# SMT-PBTSv1_4_Schematic.net
KiCad netlist of a schematic drawn in EasyEDA
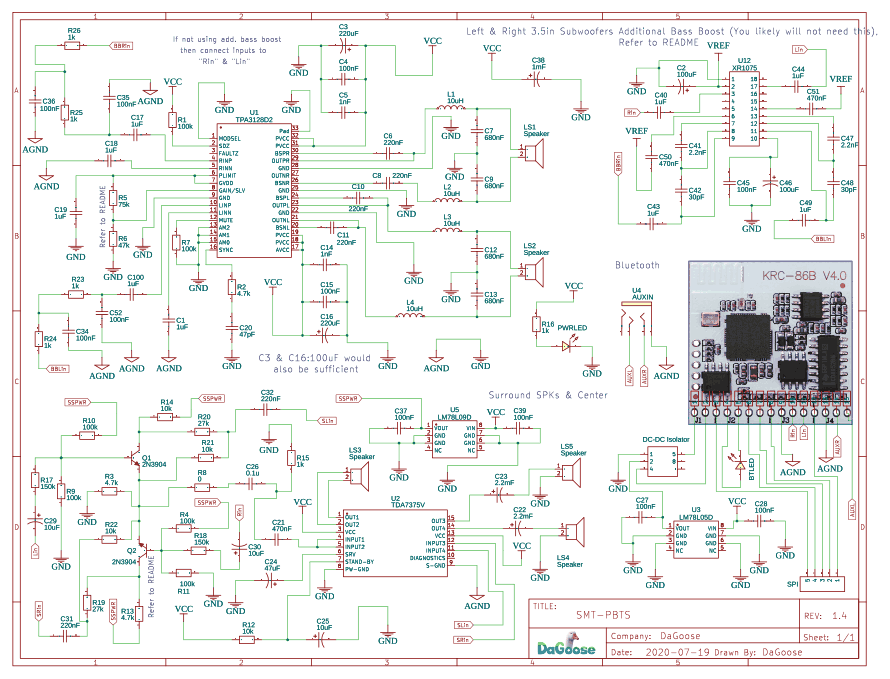
[diagram p0: schematic sheet]

(export (version "E")
  (design (tool "Eeschema 10.0.6"))
  (components
    (comp (ref "BTLED")
      (value "LED-0603_R")
      (fields
        (field (name "BOM_Manufacturer Part") "19-217/R6C-AL1M2VY/3T")
        (field (name "BOM_Supplier Part") "C72044")
      )
      (libsource (lib "") (part "LED-0603_R_1"))
    )
    (comp (ref "C1") (value "1uF") (libsource (lib "") (part "C_0603_US")))
    (comp (ref "C2") (value "100uF") (libsource (lib "") (part "C_Tan_SMD_A_US_2")))
    (comp (ref "C3") (value "220uF") (libsource (lib "") (part "C_Tan_SMD_A_US_2")))
    (comp (ref "C4") (value "100nF") (libsource (lib "") (part "C_0603_US_1")))
    (comp (ref "C5") (value "1nF") (libsource (lib "") (part "C_0603_US_1")))
    (comp (ref "C6") (value "220nF") (libsource (lib "") (part "C_0603_US_1")))
    (comp (ref "C7") (value "680nF") (libsource (lib "") (part "C_0603_US")))
    (comp (ref "C8") (value "220nF") (libsource (lib "") (part "C_0603_US_1")))
    (comp (ref "C9") (value "680nF") (libsource (lib "") (part "C_0603_US")))
    (comp (ref "C10") (value "220nF") (libsource (lib "") (part "C_0603_US_1")))
    (comp (ref "C11") (value "220nF") (libsource (lib "") (part "C_0603_US_1")))
    (comp (ref "C12") (value "680nF") (libsource (lib "") (part "C_0603_US")))
    (comp (ref "C13") (value "680nF") (libsource (lib "") (part "C_0603_US")))
    (comp (ref "C14") (value "1nF") (libsource (lib "") (part "C_0603_US_1")))
    (comp (ref "C15") (value "100nF") (libsource (lib "") (part "C_0603_US_1")))
    (comp (ref "C16") (value "220uF") (libsource (lib "") (part "C_Tan_SMD_A_US_1")))
    (comp (ref "C17") (value "1uF") (libsource (lib "") (part "C_0603_US_1")))
    (comp (ref "C18") (value "1uF") (libsource (lib "") (part "C_0603_US_1")))
    (comp (ref "C19") (value "1uF") (libsource (lib "") (part "C_0603_US")))
    (comp (ref "C20") (value "47pF") (libsource (lib "") (part "C_0603_US")))
    (comp (ref "C21") (value "470nF") (libsource (lib "") (part "C_0603_US_1")))
    (comp (ref "C22") (value "2.2mF") (libsource (lib "") (part "C_Tan_SMD_A_US")))
    (comp (ref "C23") (value "2.2mF") (libsource (lib "") (part "C_Tan_SMD_A_US")))
    (comp (ref "C24") (value "47uF") (libsource (lib "") (part "C_Tan_SMD_A_US_6")))
    (comp (ref "C25") (value "10uF") (libsource (lib "") (part "C_Tan_SMD_A_US")))
    (comp (ref "C26") (value "0.1u") (libsource (lib "") (part "C_0603_US_1")))
    (comp (ref "C27") (value "100nF") (libsource (lib "") (part "C_0603_US_1")))
    (comp (ref "C28") (value "100nF") (libsource (lib "") (part "C_0603_US_1")))
    (comp (ref "C29") (value "10uF") (libsource (lib "") (part "C_Tan_SMD_A_US_3")))
    (comp (ref "C30") (value "10uF") (libsource (lib "") (part "C_Tan_SMD_A_US_4")))
    (comp (ref "C31") (value "220nF") (libsource (lib "") (part "C_0603_US_1")))
    (comp (ref "C32") (value "220nF") (libsource (lib "") (part "C_0603_US_1")))
    (comp (ref "C34") (value "100nF") (libsource (lib "") (part "C_0603_US")))
    (comp (ref "C35") (value "100nF") (libsource (lib "") (part "C_0603_US")))
    (comp (ref "C36") (value "100nF") (libsource (lib "") (part "C_0603_US")))
    (comp (ref "C37") (value "100nF") (libsource (lib "") (part "C_0603_US_1")))
    (comp (ref "C38") (value "1mF") (libsource (lib "") (part "C_Tan_SMD_A_US_1")))
    (comp (ref "C39") (value "100nF") (libsource (lib "") (part "C_0603_US_1")))
    (comp (ref "C40") (value "1uF") (libsource (lib "") (part "C_0603_US_1")))
    (comp (ref "C41") (value "2.2nF") (libsource (lib "") (part "C_0603_US")))
    (comp (ref "C42") (value "30pF") (libsource (lib "") (part "C_0603_US")))
    (comp (ref "C43") (value "1uF") (libsource (lib "") (part "C_0603_US_2")))
    (comp (ref "C44") (value "1uF") (libsource (lib "") (part "C_0603_US_1")))
    (comp (ref "C45") (value "100nF") (libsource (lib "") (part "C_0603_US")))
    (comp (ref "C46") (value "100uF") (libsource (lib "") (part "C_Tan_SMD_A_US_5")))
    (comp (ref "C47") (value "2.2nF") (libsource (lib "") (part "C_0603_US")))
    (comp (ref "C48") (value "30pF") (libsource (lib "") (part "C_0603_US")))
    (comp (ref "C49") (value "1uF") (libsource (lib "") (part "C_0603_US_2")))
    (comp (ref "C50") (value "470nF") (libsource (lib "") (part "C_0603_US")))
    (comp (ref "C51") (value "470nF") (libsource (lib "") (part "C_0603_US_1")))
    (comp (ref "C52") (value "100nF") (libsource (lib "") (part "C_0603_US")))
    (comp (ref "C100") (value "1uF") (libsource (lib "") (part "C_0603_US_1")))
    (comp (ref "H1")
      (value "SPI")
      (fields (field (name "BOM_Supplier Part") "C50950"))
      (libsource (lib "") (part "HDR-F-2.54_1x5"))
    )
    (comp (ref "J1")
      (value "HDR-M-2.54_1x1")
      (fields (field (name "BOM_Supplier Part") "C81276"))
      (libsource (lib "") (part "HDR-M-2.54_1x1_9"))
    )
    (comp (ref "J2")
      (value "HDR-M-2.54_1x1")
      (fields (field (name "BOM_Supplier Part") "C81276"))
      (libsource (lib "") (part "HDR-M-2.54_1x1_14"))
    )
    (comp (ref "J3")
      (value "HDR-M-2.54_1x1")
      (fields (field (name "BOM_Supplier Part") "C81276"))
      (libsource (lib "") (part "HDR-M-2.54_1x1_11"))
    )
    (comp (ref "J4")
      (value "HDR-M-2.54_1x1")
      (fields (field (name "BOM_Supplier Part") "C81276"))
      (libsource (lib "") (part "HDR-M-2.54_1x1_2"))
    )
    (comp (ref "J5")
      (value "HDR-M-2.54_1x1")
      (fields (field (name "BOM_Supplier Part") "C81276"))
      (libsource (lib "") (part "HDR-M-2.54_1x1_10"))
    )
    (comp (ref "J6")
      (value "HDR-M-2.54_1x1")
      (fields (field (name "BOM_Supplier Part") "C81276"))
      (libsource (lib "") (part "HDR-M-2.54_1x1_1"))
    )
    (comp (ref "J7")
      (value "HDR-M-2.54_1x1")
      (fields (field (name "BOM_Supplier Part") "C81276"))
      (libsource (lib "") (part "HDR-M-2.54_1x1_12"))
    )
    (comp (ref "J8")
      (value "HDR-M-2.54_1x1")
      (fields (field (name "BOM_Supplier Part") "C81276"))
      (libsource (lib "") (part "HDR-M-2.54_1x1_3"))
    )
    (comp (ref "J9")
      (value "HDR-M-2.54_1x1")
      (fields (field (name "BOM_Supplier Part") "C81276"))
      (libsource (lib "") (part "HDR-M-2.54_1x1_5"))
    )
    (comp (ref "J10")
      (value "HDR-M-2.54_1x1")
      (fields (field (name "BOM_Supplier Part") "C81276"))
      (libsource (lib "") (part "HDR-M-2.54_1x1_13"))
    )
    (comp (ref "J11")
      (value "HDR-M-2.54_1x1")
      (fields (field (name "BOM_Supplier Part") "C81276"))
      (libsource (lib "") (part "HDR-M-2.54_1x1_8"))
    )
    (comp (ref "J12")
      (value "HDR-M-2.54_1x1")
      (fields (field (name "BOM_Supplier Part") "C81276"))
      (libsource (lib "") (part "HDR-M-2.54_1x1_7"))
    )
    (comp (ref "J13")
      (value "HDR-M-2.54_1x1")
      (fields (field (name "BOM_Supplier Part") "C81276"))
      (libsource (lib "") (part "HDR-M-2.54_1x1_6"))
    )
    (comp (ref "J14")
      (value "HDR-M-2.54_1x1")
      (fields (field (name "BOM_Supplier Part") "C81276"))
      (libsource (lib "") (part "HDR-M-2.54_1x1_4"))
    )
    (comp (ref "J15")
      (value "HDR-M-2.54_1x1")
      (fields (field (name "BOM_Supplier Part") "C81276"))
      (libsource (lib "") (part "HDR-M-2.54_1x1"))
    )
    (comp (ref "L1") (value "10uH") (libsource (lib "") (part "L0603_US")))
    (comp (ref "L2") (value "10uH") (libsource (lib "") (part "L0603_US")))
    (comp (ref "L3") (value "10uH") (libsource (lib "") (part "L0603_US")))
    (comp (ref "L4") (value "10uH") (libsource (lib "") (part "L0603_US")))
    (comp (ref "LS1") (value "Speaker") (libsource (lib "") (part "Speaker")))
    (comp (ref "LS2") (value "Speaker") (libsource (lib "") (part "Speaker")))
    (comp (ref "LS3") (value "Speaker") (libsource (lib "") (part "Speaker")))
    (comp (ref "LS4") (value "Speaker") (libsource (lib "") (part "Speaker")))
    (comp (ref "LS5") (value "Speaker") (libsource (lib "") (part "Speaker")))
    (comp (ref "P1")
      (value "DC-DC Isolator")
      (fields
        (field (name "BOM_Manufacturer Part") "2X3 2.54mm IDC Box")
        (field (name "BOM_Supplier Part") "C11214")
      )
      (libsource (lib "") (part "HDR-IDC-2.54-2X3P"))
    )
    (comp (ref "PWRLED")
      (value "LED-0603_R")
      (fields
        (field (name "BOM_Manufacturer Part") "19-217/R6C-AL1M2VY/3T")
        (field (name "BOM_Supplier Part") "C72044")
      )
      (libsource (lib "") (part "LED-0603_R"))
    )
    (comp (ref "Q1")
      (value "2N3904")
      (fields
        (field (name "BOM_Manufacturer Part") "2n3904S-RTK/PS")
        (field (name "BOM_Supplier Part") "C18536")
      )
      (libsource (lib "") (part "2N3904(SOT-23)"))
    )
    (comp (ref "Q2")
      (value "2N3904")
      (fields
        (field (name "BOM_Manufacturer Part") "2n3904S-RTK/PS")
        (field (name "BOM_Supplier Part") "C18536")
      )
      (libsource (lib "") (part "2N3904(SOT-23)_1"))
    )
    (comp (ref "R1") (value "100k") (libsource (lib "") (part "R_0201_EU")))
    (comp (ref "R2") (value "4.7k") (libsource (lib "") (part "R_0201_EU")))
    (comp (ref "R3") (value "4.7k") (libsource (lib "") (part "R_0603_EU_2")))
    (comp (ref "R4") (value "100k") (libsource (lib "") (part "R_0603_EU")))
    (comp (ref "R5") (value "75k") (libsource (lib "") (part "R_0603_EU_1")))
    (comp (ref "R6") (value "47k") (libsource (lib "") (part "R_0603_EU_1")))
    (comp (ref "R7") (value "100k") (libsource (lib "") (part "R_0603_EU_1")))
    (comp (ref "R8") (value "0") (libsource (lib "") (part "R_0603_EU")))
    (comp (ref "R9") (value "100k") (libsource (lib "") (part "R_0603_EU_1")))
    (comp (ref "R10") (value "100k") (libsource (lib "") (part "R_0603_EU")))
    (comp (ref "R11") (value "100k") (libsource (lib "") (part "R_0603_EU")))
    (comp (ref "R12") (value "10k") (libsource (lib "") (part "R_0603_EU")))
    (comp (ref "R13") (value "4.7k") (libsource (lib "") (part "R_0603_EU_1")))
    (comp (ref "R14") (value "10k") (libsource (lib "") (part "R_0603_EU")))
    (comp (ref "R15") (value "1k") (libsource (lib "") (part "R_0603_EU_1")))
    (comp (ref "R16") (value "1k") (libsource (lib "") (part "R_0603_EU_1")))
    (comp (ref "R17") (value "150k") (libsource (lib "") (part "R_0603_EU_1")))
    (comp (ref "R18") (value "150k") (libsource (lib "") (part "R_0603_EU")))
    (comp (ref "R19") (value "27k") (libsource (lib "") (part "R_0603_EU_1")))
    (comp (ref "R20") (value "27k") (libsource (lib "") (part "R_0603_EU")))
    (comp (ref "R21") (value "10k") (libsource (lib "") (part "R_0603_EU")))
    (comp (ref "R22") (value "10k") (libsource (lib "") (part "R_0603_EU")))
    (comp (ref "R23") (value "1k") (libsource (lib "") (part "R_0603_EU")))
    (comp (ref "R24") (value "1k") (libsource (lib "") (part "R_0603_EU_1")))
    (comp (ref "R25") (value "1k") (libsource (lib "") (part "R_0603_EU_1")))
    (comp (ref "R26") (value "1k") (libsource (lib "") (part "R_0603_EU")))
    (comp (ref "U1")
      (value "TPA3128D2")
      (fields
        (field (name "BOM_Manufacturer Part") "TPA3128D2DAPR")
        (field (name "BOM_Supplier Part") "C473362")
      )
      (libsource (lib "") (part "TPA3128D2DAPR"))
    )
    (comp (ref "U2")
      (value "TDA7375V")
      (fields
        (field (name "BOM_Manufacturer Part") "E-TDA7375V")
        (field (name "BOM_Supplier Part") "C262883")
      )
      (libsource (lib "") (part "E-TDA7375V"))
    )
    (comp (ref "U3")
      (value "LM78L05D")
      (fields (field (name "BOM_Supplier Part") "C596351"))
      (libsource (lib "") (part "LM78L05D"))
    )
    (comp (ref "U4") (value "AUXIN") (libsource (lib "") (part "AUDIO-JACK3")))
    (comp (ref "U5")
      (value "LM78L09D")
      (fields (field (name "BOM_Manufacturer Part") "LM78L05D") (field (name "BOM_Supplier Part") "C596351"))
      (libsource (lib "") (part "LM78L05D"))
    )
    (comp (ref "U12")
      (value "XR1075")
      (fields
        (field (name "BOM_Manufacturer Part") "2X9 2.54mm IDC Box")
        (field (name "BOM_Supplier Part") "C11216")
      )
      (libsource (lib "") (part "HDR-IDC-2.54-2X9P"))
    )
  )
  (nets
    (net (code "1") (name "AGND") (class "Default")
      (node (ref "C1") (pin "1") (pinfunction "1_1") (pintype "unspecified"))
      (node (ref "C12") (pin "1") (pinfunction "1_1") (pintype "unspecified"))
      (node (ref "C13") (pin "2") (pinfunction "2_2") (pintype "unspecified"))
      (node (ref "C14") (pin "2") (pinfunction "2_2") (pintype "unspecified"))
      (node (ref "C15") (pin "2") (pinfunction "2_2") (pintype "unspecified"))
      (node (ref "C16") (pin "2") (pinfunction "2_2") (pintype "unspecified"))
      (node (ref "C18") (pin "1") (pinfunction "1_1") (pintype "unspecified"))
      (node (ref "C19") (pin "1") (pinfunction "1_1") (pintype "unspecified"))
      (node (ref "C2") (pin "2") (pinfunction "2_2") (pintype "unspecified"))
      (node (ref "C20") (pin "1") (pinfunction "1_1") (pintype "unspecified"))
      (node (ref "C24") (pin "2") (pinfunction "2_2") (pintype "unspecified"))
      (node (ref "C25") (pin "2") (pinfunction "2_2") (pintype "unspecified"))
      (node (ref "C27") (pin "1") (pinfunction "1_1") (pintype "unspecified"))
      (node (ref "C28") (pin "2") (pinfunction "2_2") (pintype "unspecified"))
      (node (ref "C3") (pin "2") (pinfunction "2_2") (pintype "unspecified"))
      (node (ref "C34") (pin "1") (pinfunction "1_1") (pintype "unspecified"))
      (node (ref "C35") (pin "2") (pinfunction "2_2") (pintype "unspecified"))
      (node (ref "C36") (pin "1") (pinfunction "1_1") (pintype "unspecified"))
      (node (ref "C37") (pin "1") (pinfunction "1_1") (pintype "unspecified"))
      (node (ref "C38") (pin "2") (pinfunction "2_2") (pintype "unspecified"))
      (node (ref "C39") (pin "2") (pinfunction "2_2") (pintype "unspecified"))
      (node (ref "C4") (pin "1") (pinfunction "1_1") (pintype "unspecified"))
      (node (ref "C45") (pin "1") (pinfunction "1_1") (pintype "unspecified"))
      (node (ref "C46") (pin "2") (pinfunction "2_2") (pintype "unspecified"))
      (node (ref "C5") (pin "1") (pinfunction "1_1") (pintype "unspecified"))
      (node (ref "C52") (pin "1") (pinfunction "1_1") (pintype "unspecified"))
      (node (ref "C7") (pin "1") (pinfunction "1_1") (pintype "unspecified"))
      (node (ref "C9") (pin "2") (pinfunction "2_2") (pintype "unspecified"))
      (node (ref "J13") (pin "1") (pinfunction "13_1") (pintype "input"))
      (node (ref "J9") (pin "1") (pinfunction "9_1") (pintype "input"))
      (node (ref "LS4") (pin "2") (pinfunction "2_2") (pintype "input"))
      (node (ref "LS5") (pin "2") (pinfunction "2_2") (pintype "input"))
      (node (ref "P1") (pin "1") (pinfunction "1_1") (pintype "unspecified"))
      (node (ref "PWRLED") (pin "2") (pinfunction "2_2") (pintype "unspecified"))
      (node (ref "R11") (pin "2") (pinfunction "2_2") (pintype "unspecified"))
      (node (ref "R15") (pin "2") (pinfunction "2_2") (pintype "unspecified"))
      (node (ref "R3") (pin "2") (pinfunction "2_2") (pintype "unspecified"))
      (node (ref "R6") (pin "1") (pinfunction "1_1") (pintype "unspecified"))
      (node (ref "R7") (pin "1") (pinfunction "1_1") (pintype "unspecified"))
      (node (ref "R9") (pin "1") (pinfunction "1_1") (pintype "unspecified"))
      (node (ref "U1") (pin "1") (pinfunction "MODSEL_1") (pintype "unspecified"))
      (node (ref "U1") (pin "13") (pinfunction "AM2_13") (pintype "unspecified"))
      (node (ref "U1") (pin "14") (pinfunction "AM1_14") (pintype "unspecified"))
      (node (ref "U1") (pin "15") (pinfunction "AM0_15") (pintype "unspecified"))
      (node (ref "U1") (pin "22") (pinfunction "GND_22") (pintype "unspecified"))
      (node (ref "U1") (pin "25") (pinfunction "GND_25") (pintype "unspecified"))
      (node (ref "U1") (pin "28") (pinfunction "GND_28") (pintype "unspecified"))
      (node (ref "U1") (pin "33") (pinfunction "Pad_33") (pintype "unspecified"))
      (node (ref "U1") (pin "9") (pinfunction "GND_9") (pintype "unspecified"))
      (node (ref "U12") (pin "1") (pinfunction "1_1") (pintype "unspecified"))
      (node (ref "U2") (pin "8") (pinfunction "PW-GND_8") (pintype "unspecified"))
      (node (ref "U2") (pin "9") (pinfunction "S-GND_9") (pintype "unspecified"))
      (node (ref "U3") (pin "2") (pinfunction "GND_2") (pintype "unspecified"))
      (node (ref "U3") (pin "3") (pinfunction "GND_3") (pintype "unspecified"))
      (node (ref "U3") (pin "6") (pinfunction "GND_6") (pintype "unspecified"))
      (node (ref "U3") (pin "7") (pinfunction "GND_7") (pintype "unspecified"))
      (node (ref "U4") (pin "EARTH") (pinfunction "EARTH_EARTH") (pintype "unspecified"))
      (node (ref "U5") (pin "2") (pinfunction "GND_2") (pintype "unspecified"))
      (node (ref "U5") (pin "3") (pinfunction "GND_3") (pintype "unspecified"))
      (node (ref "U5") (pin "6") (pinfunction "GND_6") (pintype "unspecified"))
      (node (ref "U5") (pin "7") (pinfunction "GND_7") (pintype "unspecified"))
    )
    (net (code "2") (name "AUXL") (class "Default")
      (node (ref "J15") (pin "1") (pinfunction "15_1") (pintype "input"))
      (node (ref "U4") (pin "TIP") (pinfunction "TIP_TIP") (pintype "unspecified"))
    )
    (net (code "3") (name "AUXR") (class "Default")
      (node (ref "J14") (pin "1") (pinfunction "14_1") (pintype "input"))
      (node (ref "U4") (pin "RING1") (pinfunction "RING1_RING1") (pintype "unspecified"))
    )
    (net (code "4") (name "BBLin") (class "Default")
      (node (ref "C49") (pin "2") (pinfunction "2_2") (pintype "unspecified"))
      (node (ref "R24") (pin "1") (pinfunction "1_1") (pintype "unspecified"))
    )
    (net (code "5") (name "BBRin") (class "Default")
      (node (ref "C43") (pin "2") (pinfunction "2_2") (pintype "unspecified"))
      (node (ref "R26") (pin "2") (pinfunction "2_2") (pintype "unspecified"))
    )
    (net (code "6") (name "Lin") (class "Default")
      (node (ref "C29") (pin "2") (pinfunction "2_2") (pintype "unspecified"))
      (node (ref "C44") (pin "2") (pinfunction "2_2") (pintype "unspecified"))
      (node (ref "J11") (pin "1") (pinfunction "11_1") (pintype "input"))
    )
    (net (code "7") (name "Net-(C7-Pad2)") (class "Default")
      (node (ref "C7") (pin "2") (pinfunction "2_2") (pintype "unspecified"))
      (node (ref "L1") (pin "2") (pinfunction "2_2") (pintype "unspecified"))
      (node (ref "LS1") (pin "1") (pinfunction "1_1") (pintype "input"))
    )
    (net (code "8") (name "Net-(C8-Pad2)") (class "Default")
      (node (ref "C8") (pin "2") (pinfunction "2_2") (pintype "unspecified"))
      (node (ref "L2") (pin "1") (pinfunction "1_1") (pintype "unspecified"))
    )
    (net (code "9") (name "Net-(C9-Pad1)") (class "Default")
      (node (ref "C9") (pin "1") (pinfunction "1_1") (pintype "unspecified"))
      (node (ref "L2") (pin "2") (pinfunction "2_2") (pintype "unspecified"))
      (node (ref "LS1") (pin "2") (pinfunction "2_2") (pintype "input"))
    )
    (net (code "10") (name "Net-(C12-Pad2)") (class "Default")
      (node (ref "C12") (pin "2") (pinfunction "2_2") (pintype "unspecified"))
      (node (ref "L3") (pin "2") (pinfunction "2_2") (pintype "unspecified"))
      (node (ref "LS2") (pin "1") (pinfunction "1_1") (pintype "input"))
    )
    (net (code "11") (name "Net-(C13-Pad1)") (class "Default")
      (node (ref "C13") (pin "1") (pinfunction "1_1") (pintype "unspecified"))
      (node (ref "L4") (pin "2") (pinfunction "2_2") (pintype "unspecified"))
      (node (ref "LS2") (pin "2") (pinfunction "2_2") (pintype "input"))
    )
    (net (code "12") (name "Net-(C17-Pad1)") (class "Default")
      (node (ref "C17") (pin "1") (pinfunction "1_1") (pintype "unspecified"))
      (node (ref "C35") (pin "1") (pinfunction "1_1") (pintype "unspecified"))
      (node (ref "R25") (pin "1") (pinfunction "1_1") (pintype "unspecified"))
    )
    (net (code "13") (name "Net-(C20-Pad2)") (class "Default")
      (node (ref "C20") (pin "2") (pinfunction "2_2") (pintype "unspecified"))
      (node (ref "R2") (pin "1") (pinfunction "1_1") (pintype "unspecified"))
    )
    (net (code "14") (name "Net-(C21-Pad1)") (class "Default")
      (node (ref "C21") (pin "1") (pinfunction "1_1") (pintype "unspecified"))
      (node (ref "C26") (pin "2") (pinfunction "2_2") (pintype "unspecified"))
      (node (ref "R15") (pin "1") (pinfunction "1_1") (pintype "unspecified"))
    )
    (net (code "15") (name "Net-(C22-Pad2)") (class "Default")
      (node (ref "C22") (pin "2") (pinfunction "2_2") (pintype "unspecified"))
      (node (ref "LS4") (pin "1") (pinfunction "1_1") (pintype "input"))
    )
    (net (code "16") (name "Net-(C23-Pad2)") (class "Default")
      (node (ref "C23") (pin "2") (pinfunction "2_2") (pintype "unspecified"))
      (node (ref "LS5") (pin "1") (pinfunction "1_1") (pintype "input"))
    )
    (net (code "17") (name "Net-(C26-Pad1)") (class "Default")
      (node (ref "C26") (pin "1") (pinfunction "1_1") (pintype "unspecified"))
      (node (ref "R8") (pin "2") (pinfunction "2_2") (pintype "unspecified"))
    )
    (net (code "18") (name "Net-(C29-Pad1)") (class "Default")
      (node (ref "C29") (pin "1") (pinfunction "1_1") (pintype "unspecified"))
      (node (ref "R17") (pin "1") (pinfunction "1_1") (pintype "unspecified"))
    )
    (net (code "19") (name "Net-(C30-Pad1)") (class "Default")
      (node (ref "C30") (pin "1") (pinfunction "1_1") (pintype "unspecified"))
      (node (ref "R18") (pin "2") (pinfunction "2_2") (pintype "unspecified"))
    )
    (net (code "20") (name "Net-(C31-Pad2)") (class "Default")
      (node (ref "C31") (pin "2") (pinfunction "2_2") (pintype "unspecified"))
      (node (ref "R19") (pin "1") (pinfunction "1_1") (pintype "unspecified"))
      (node (ref "R22") (pin "1") (pinfunction "1_1") (pintype "unspecified"))
    )
    (net (code "21") (name "Net-(C32-Pad1)") (class "Default")
      (node (ref "C32") (pin "1") (pinfunction "1_1") (pintype "unspecified"))
      (node (ref "R20") (pin "2") (pinfunction "2_2") (pintype "unspecified"))
      (node (ref "R21") (pin "2") (pinfunction "2_2") (pintype "unspecified"))
    )
    (net (code "22") (name "Net-(C34-Pad2)") (class "Default")
      (node (ref "C34") (pin "2") (pinfunction "2_2") (pintype "unspecified"))
      (node (ref "R23") (pin "1") (pinfunction "1_1") (pintype "unspecified"))
      (node (ref "R24") (pin "2") (pinfunction "2_2") (pintype "unspecified"))
    )
    (net (code "23") (name "Net-(C36-Pad2)") (class "Default")
      (node (ref "C36") (pin "2") (pinfunction "2_2") (pintype "unspecified"))
      (node (ref "R25") (pin "2") (pinfunction "2_2") (pintype "unspecified"))
      (node (ref "R26") (pin "1") (pinfunction "1_1") (pintype "unspecified"))
    )
    (net (code "24") (name "Net-(C100-Pad1)") (class "Default")
      (node (ref "C100") (pin "1") (pinfunction "1_1") (pintype "unspecified"))
      (node (ref "C52") (pin "2") (pinfunction "2_2") (pintype "unspecified"))
      (node (ref "R23") (pin "2") (pinfunction "2_2") (pintype "unspecified"))
    )
    (net (code "25") (name "Net-(J2-2)") (class "Default")
      (node (ref "J2") (pin "1") (pinfunction "2_1") (pintype "input"))
      (node (ref "P1") (pin "5") (pinfunction "4_5") (pintype "unspecified"))
    )
    (net (code "26") (name "Net-(J3-3)") (class "Default")
      (node (ref "H1") (pin "5") (pinfunction "5_5") (pintype "unspecified"))
      (node (ref "J3") (pin "1") (pinfunction "3_1") (pintype "input"))
    )
    (net (code "27") (name "Net-(J4-4)") (class "Default")
      (node (ref "BTLED") (pin "1") (pinfunction "1_1") (pintype "unspecified"))
      (node (ref "J4") (pin "1") (pinfunction "4_1") (pintype "input"))
    )
    (net (code "28") (name "Net-(J5-5)") (class "Default")
      (node (ref "BTLED") (pin "2") (pinfunction "2_2") (pintype "unspecified"))
      (node (ref "J5") (pin "1") (pinfunction "5_1") (pintype "input"))
    )
    (net (code "29") (name "Net-(J6-6)") (class "Default")
      (node (ref "H1") (pin "4") (pinfunction "4_4") (pintype "unspecified"))
      (node (ref "J6") (pin "1") (pinfunction "6_1") (pintype "input"))
    )
    (net (code "30") (name "Net-(J7-7)") (class "Default")
      (node (ref "H1") (pin "3") (pinfunction "3_3") (pintype "unspecified"))
      (node (ref "J7") (pin "1") (pinfunction "7_1") (pintype "input"))
    )
    (net (code "31") (name "Net-(J8-8)") (class "Default")
      (node (ref "H1") (pin "2") (pinfunction "2_2") (pintype "unspecified"))
      (node (ref "J8") (pin "1") (pinfunction "8_1") (pintype "input"))
    )
    (net (code "32") (name "Net-(J12-12)") (class "Default")
      (node (ref "H1") (pin "1") (pinfunction "1_1") (pintype "unspecified"))
      (node (ref "J12") (pin "1") (pinfunction "12_1") (pintype "input"))
    )
    (net (code "33") (name "Net-(P1-2)") (class "Default")
      (node (ref "C27") (pin "2") (pinfunction "2_2") (pintype "unspecified"))
      (node (ref "P1") (pin "3") (pinfunction "2_3") (pintype "unspecified"))
      (node (ref "U3") (pin "1") (pinfunction "VOUT_1") (pintype "unspecified"))
    )
    (net (code "34") (name "Net-(P1-5)") (class "Default")
      (node (ref "J1") (pin "1") (pinfunction "1_1") (pintype "input"))
      (node (ref "P1") (pin "2") (pinfunction "5_2") (pintype "unspecified"))
    )
    (net (code "35") (name "Net-(PWRLED-Pad1)") (class "Default")
      (node (ref "PWRLED") (pin "1") (pinfunction "1_1") (pintype "unspecified"))
      (node (ref "R16") (pin "1") (pinfunction "1_1") (pintype "unspecified"))
    )
    (net (code "36") (name "Net-(Q1-B)") (class "Default")
      (node (ref "Q1") (pin "2") (pinfunction "B_2") (pintype "input"))
      (node (ref "R10") (pin "1") (pinfunction "1_1") (pintype "unspecified"))
      (node (ref "R17") (pin "2") (pinfunction "2_2") (pintype "unspecified"))
      (node (ref "R9") (pin "2") (pinfunction "2_2") (pintype "unspecified"))
    )
    (net (code "37") (name "Net-(Q1-C)") (class "Default")
      (node (ref "Q1") (pin "3") (pinfunction "C_3") (pintype "input"))
      (node (ref "R14") (pin "1") (pinfunction "1_1") (pintype "unspecified"))
      (node (ref "R20") (pin "1") (pinfunction "1_1") (pintype "unspecified"))
    )
    (net (code "38") (name "Net-(Q1-E)") (class "Default")
      (node (ref "Q1") (pin "1") (pinfunction "E_1") (pintype "input"))
      (node (ref "Q2") (pin "1") (pinfunction "E_1") (pintype "input"))
      (node (ref "R21") (pin "1") (pinfunction "1_1") (pintype "unspecified"))
      (node (ref "R22") (pin "2") (pinfunction "2_2") (pintype "unspecified"))
      (node (ref "R3") (pin "1") (pinfunction "1_1") (pintype "unspecified"))
      (node (ref "R8") (pin "1") (pinfunction "1_1") (pintype "unspecified"))
    )
    (net (code "39") (name "Net-(Q2-B)") (class "Default")
      (node (ref "Q2") (pin "2") (pinfunction "B_2") (pintype "input"))
      (node (ref "R11") (pin "1") (pinfunction "1_1") (pintype "unspecified"))
      (node (ref "R18") (pin "1") (pinfunction "1_1") (pintype "unspecified"))
      (node (ref "R4") (pin "1") (pinfunction "1_1") (pintype "unspecified"))
    )
    (net (code "40") (name "Net-(Q2-C)") (class "Default")
      (node (ref "Q2") (pin "3") (pinfunction "C_3") (pintype "input"))
      (node (ref "R13") (pin "2") (pinfunction "2_2") (pintype "unspecified"))
      (node (ref "R19") (pin "2") (pinfunction "2_2") (pintype "unspecified"))
    )
    (net (code "41") (name "Net-(U1-BSNL)") (class "Default")
      (node (ref "C11") (pin "1") (pinfunction "1_1") (pintype "unspecified"))
      (node (ref "U1") (pin "20") (pinfunction "BSNL_20") (pintype "unspecified"))
    )
    (net (code "42") (name "Net-(U1-BSNR)") (class "Default")
      (node (ref "C8") (pin "1") (pinfunction "1_1") (pintype "unspecified"))
      (node (ref "U1") (pin "26") (pinfunction "BSNR_26") (pintype "unspecified"))
    )
    (net (code "43") (name "Net-(U1-BSPL)") (class "Default")
      (node (ref "C10") (pin "1") (pinfunction "1_1") (pintype "unspecified"))
      (node (ref "U1") (pin "24") (pinfunction "BSPL_24") (pintype "unspecified"))
    )
    (net (code "44") (name "Net-(U1-BSPR)") (class "Default")
      (node (ref "C6") (pin "1") (pinfunction "1_1") (pintype "unspecified"))
      (node (ref "U1") (pin "30") (pinfunction "BSPR_30") (pintype "unspecified"))
    )
    (net (code "45") (name "Net-(U1-GAIN{slash}SLV)") (class "Default")
      (node (ref "R5") (pin "1") (pinfunction "1_1") (pintype "unspecified"))
      (node (ref "R6") (pin "2") (pinfunction "2_2") (pintype "unspecified"))
      (node (ref "U1") (pin "8") (pinfunction "GAIN/SLV_8") (pintype "unspecified"))
    )
    (net (code "46") (name "Net-(U1-GVDD)") (class "Default")
      (node (ref "C19") (pin "2") (pinfunction "2_2") (pintype "unspecified"))
      (node (ref "R5") (pin "2") (pinfunction "2_2") (pintype "unspecified"))
      (node (ref "U1") (pin "6") (pinfunction "PLIMIT_6") (pintype "unspecified"))
      (node (ref "U1") (pin "7") (pinfunction "GVDD_7") (pintype "unspecified"))
    )
    (net (code "47") (name "Net-(U1-LINN)") (class "Default")
      (node (ref "C1") (pin "2") (pinfunction "2_2") (pintype "unspecified"))
      (node (ref "U1") (pin "11") (pinfunction "LINN_11") (pintype "unspecified"))
    )
    (net (code "48") (name "Net-(U1-LINP)") (class "Default")
      (node (ref "C100") (pin "2") (pinfunction "2_2") (pintype "unspecified"))
      (node (ref "U1") (pin "10") (pinfunction "LINP_10") (pintype "unspecified"))
    )
    (net (code "49") (name "Net-(U1-MUTE)") (class "Default")
      (node (ref "R7") (pin "2") (pinfunction "2_2") (pintype "unspecified"))
      (node (ref "U1") (pin "12") (pinfunction "MUTE_12") (pintype "unspecified"))
    )
    (net (code "50") (name "Net-(U1-OUTNL)") (class "Default")
      (node (ref "C11") (pin "2") (pinfunction "2_2") (pintype "unspecified"))
      (node (ref "L4") (pin "1") (pinfunction "1_1") (pintype "unspecified"))
      (node (ref "U1") (pin "21") (pinfunction "OUTNL_21") (pintype "unspecified"))
    )
    (net (code "51") (name "Net-(U1-OUTPL)") (class "Default")
      (node (ref "C10") (pin "2") (pinfunction "2_2") (pintype "unspecified"))
      (node (ref "L3") (pin "1") (pinfunction "1_1") (pintype "unspecified"))
      (node (ref "U1") (pin "23") (pinfunction "OUTPL_23") (pintype "unspecified"))
    )
    (net (code "52") (name "Net-(U1-OUTPR)") (class "Default")
      (node (ref "C6") (pin "2") (pinfunction "2_2") (pintype "unspecified"))
      (node (ref "L1") (pin "1") (pinfunction "1_1") (pintype "unspecified"))
      (node (ref "U1") (pin "29") (pinfunction "OUTPR_29") (pintype "unspecified"))
    )
    (net (code "53") (name "Net-(U1-RINN)") (class "Default")
      (node (ref "C18") (pin "2") (pinfunction "2_2") (pintype "unspecified"))
      (node (ref "U1") (pin "5") (pinfunction "RINN_5") (pintype "unspecified"))
    )
    (net (code "54") (name "Net-(U1-RINP)") (class "Default")
      (node (ref "C17") (pin "2") (pinfunction "2_2") (pintype "unspecified"))
      (node (ref "U1") (pin "4") (pinfunction "RINP_4") (pintype "unspecified"))
    )
    (net (code "55") (name "Net-(U1-SDZ)") (class "Default")
      (node (ref "R1") (pin "1") (pinfunction "1_1") (pintype "unspecified"))
      (node (ref "U1") (pin "2") (pinfunction "SDZ_2") (pintype "unspecified"))
    )
    (net (code "56") (name "Net-(U1-SYNC)") (class "Default")
      (node (ref "R2") (pin "2") (pinfunction "2_2") (pintype "unspecified"))
      (node (ref "U1") (pin "16") (pinfunction "SYNC_16") (pintype "unspecified"))
    )
    (net (code "57") (name "Net-(U2-INPUT1)") (class "Default")
      (node (ref "C21") (pin "2") (pinfunction "2_2") (pintype "unspecified"))
      (node (ref "U2") (pin "4") (pinfunction "INPUT1_4") (pintype "unspecified"))
      (node (ref "U2") (pin "5") (pinfunction "INPUT2_5") (pintype "unspecified"))
    )
    (net (code "58") (name "Net-(U2-OUT1)") (class "Default")
      (node (ref "LS3") (pin "2") (pinfunction "2_2") (pintype "input"))
      (node (ref "U2") (pin "1") (pinfunction "OUT1_1") (pintype "unspecified"))
    )
    (net (code "59") (name "Net-(U2-OUT2)") (class "Default")
      (node (ref "LS3") (pin "1") (pinfunction "1_1") (pintype "input"))
      (node (ref "U2") (pin "2") (pinfunction "OUT2_2") (pintype "unspecified"))
    )
    (net (code "60") (name "Net-(U2-OUT3)") (class "Default")
      (node (ref "C23") (pin "1") (pinfunction "1_1") (pintype "unspecified"))
      (node (ref "U2") (pin "15") (pinfunction "OUT3_15") (pintype "unspecified"))
    )
    (net (code "61") (name "Net-(U2-OUT4)") (class "Default")
      (node (ref "C22") (pin "1") (pinfunction "1_1") (pintype "unspecified"))
      (node (ref "U2") (pin "14") (pinfunction "OUT4_14") (pintype "unspecified"))
    )
    (net (code "62") (name "Net-(U2-SRV)") (class "Default")
      (node (ref "C24") (pin "1") (pinfunction "1_1") (pintype "unspecified"))
      (node (ref "U2") (pin "6") (pinfunction "SRV_6") (pintype "unspecified"))
    )
    (net (code "63") (name "Net-(U2-STAND-BY)") (class "Default")
      (node (ref "C25") (pin "1") (pinfunction "1_1") (pintype "unspecified"))
      (node (ref "R12") (pin "2") (pinfunction "2_2") (pintype "unspecified"))
      (node (ref "U2") (pin "7") (pinfunction "STAND-BY_7") (pintype "unspecified"))
    )
    (net (code "64") (name "Net-(U12-3)") (class "Default")
      (node (ref "C40") (pin "2") (pinfunction "2_2") (pintype "unspecified"))
      (node (ref "U12") (pin "5") (pinfunction "3_5") (pintype "unspecified"))
    )
    (net (code "65") (name "Net-(U12-6)") (class "Default")
      (node (ref "C50") (pin "2") (pinfunction "2_2") (pintype "unspecified"))
      (node (ref "U12") (pin "11") (pinfunction "6_11") (pintype "unspecified"))
    )
    (net (code "66") (name "Net-(U12-7)") (class "Default")
      (node (ref "C41") (pin "2") (pinfunction "2_2") (pintype "unspecified"))
      (node (ref "U12") (pin "13") (pinfunction "7_13") (pintype "unspecified"))
    )
    (net (code "67") (name "Net-(U12-8)") (class "Default")
      (node (ref "C41") (pin "1") (pinfunction "1_1") (pintype "unspecified"))
      (node (ref "C42") (pin "2") (pinfunction "2_2") (pintype "unspecified"))
      (node (ref "U12") (pin "15") (pinfunction "8_15") (pintype "unspecified"))
    )
    (net (code "68") (name "Net-(U12-9)") (class "Default")
      (node (ref "C42") (pin "1") (pinfunction "1_1") (pintype "unspecified"))
      (node (ref "C43") (pin "1") (pinfunction "1_1") (pintype "unspecified"))
      (node (ref "U12") (pin "17") (pinfunction "9_17") (pintype "unspecified"))
    )
    (net (code "69") (name "Net-(U12-10)") (class "Default")
      (node (ref "C45") (pin "2") (pinfunction "2_2") (pintype "unspecified"))
      (node (ref "C46") (pin "1") (pinfunction "1_1") (pintype "unspecified"))
      (node (ref "U12") (pin "18") (pinfunction "10_18") (pintype "unspecified"))
    )
    (net (code "70") (name "Net-(U12-11)") (class "Default")
      (node (ref "C48") (pin "1") (pinfunction "1_1") (pintype "unspecified"))
      (node (ref "C49") (pin "1") (pinfunction "1_1") (pintype "unspecified"))
      (node (ref "U12") (pin "16") (pinfunction "11_16") (pintype "unspecified"))
    )
    (net (code "71") (name "Net-(U12-12)") (class "Default")
      (node (ref "C47") (pin "1") (pinfunction "1_1") (pintype "unspecified"))
      (node (ref "C48") (pin "2") (pinfunction "2_2") (pintype "unspecified"))
      (node (ref "U12") (pin "14") (pinfunction "12_14") (pintype "unspecified"))
    )
    (net (code "72") (name "Net-(U12-13)") (class "Default")
      (node (ref "C47") (pin "2") (pinfunction "2_2") (pintype "unspecified"))
      (node (ref "U12") (pin "12") (pinfunction "13_12") (pintype "unspecified"))
    )
    (net (code "73") (name "Net-(U12-14)") (class "Default")
      (node (ref "C51") (pin "1") (pinfunction "1_1") (pintype "unspecified"))
      (node (ref "U12") (pin "10") (pinfunction "14_10") (pintype "unspecified"))
    )
    (net (code "74") (name "Net-(U12-17)") (class "Default")
      (node (ref "C44") (pin "1") (pinfunction "1_1") (pintype "unspecified"))
      (node (ref "U12") (pin "4") (pinfunction "17_4") (pintype "unspecified"))
    )
    (net (code "75") (name "Rin") (class "Default")
      (node (ref "C30") (pin "2") (pinfunction "2_2") (pintype "unspecified"))
      (node (ref "C40") (pin "1") (pinfunction "1_1") (pintype "unspecified"))
      (node (ref "J10") (pin "1") (pinfunction "10_1") (pintype "input"))
    )
    (net (code "76") (name "SLin") (class "Default")
      (node (ref "C32") (pin "2") (pinfunction "2_2") (pintype "unspecified"))
      (node (ref "U2") (pin "11") (pinfunction "INPUT4_11") (pintype "unspecified"))
    )
    (net (code "77") (name "SRin") (class "Default")
      (node (ref "C31") (pin "1") (pinfunction "1_1") (pintype "unspecified"))
      (node (ref "U2") (pin "12") (pinfunction "INPUT3_12") (pintype "unspecified"))
    )
    (net (code "78") (name "SSPWR") (class "Default")
      (node (ref "C37") (pin "2") (pinfunction "2_2") (pintype "unspecified"))
      (node (ref "R10") (pin "2") (pinfunction "2_2") (pintype "unspecified"))
      (node (ref "R13") (pin "1") (pinfunction "1_1") (pintype "unspecified"))
      (node (ref "R14") (pin "2") (pinfunction "2_2") (pintype "unspecified"))
      (node (ref "R4") (pin "2") (pinfunction "2_2") (pintype "unspecified"))
      (node (ref "U5") (pin "1") (pinfunction "VOUT_1") (pintype "unspecified"))
    )
    (net (code "79") (name "VCC") (class "Default")
      (node (ref "C14") (pin "1") (pinfunction "1_1") (pintype "unspecified"))
      (node (ref "C15") (pin "1") (pinfunction "1_1") (pintype "unspecified"))
      (node (ref "C16") (pin "1") (pinfunction "1_1") (pintype "unspecified"))
      (node (ref "C28") (pin "1") (pinfunction "1_1") (pintype "unspecified"))
      (node (ref "C3") (pin "1") (pinfunction "1_1") (pintype "unspecified"))
      (node (ref "C38") (pin "1") (pinfunction "1_1") (pintype "unspecified"))
      (node (ref "C39") (pin "1") (pinfunction "1_1") (pintype "unspecified"))
      (node (ref "C4") (pin "2") (pinfunction "2_2") (pintype "unspecified"))
      (node (ref "C5") (pin "2") (pinfunction "2_2") (pintype "unspecified"))
      (node (ref "R1") (pin "2") (pinfunction "2_2") (pintype "unspecified"))
      (node (ref "R12") (pin "1") (pinfunction "1_1") (pintype "unspecified"))
      (node (ref "R16") (pin "2") (pinfunction "2_2") (pintype "unspecified"))
      (node (ref "U1") (pin "17") (pinfunction "AVCC_17") (pintype "unspecified"))
      (node (ref "U1") (pin "18") (pinfunction "PVCC_18") (pintype "unspecified"))
      (node (ref "U1") (pin "19") (pinfunction "PVCC_19") (pintype "unspecified"))
      (node (ref "U1") (pin "31") (pinfunction "PVCC_31") (pintype "unspecified"))
      (node (ref "U1") (pin "32") (pinfunction "PVCC_32") (pintype "unspecified"))
      (node (ref "U2") (pin "13") (pinfunction "VCC_13") (pintype "unspecified"))
      (node (ref "U2") (pin "3") (pinfunction "VCC_3") (pintype "unspecified"))
      (node (ref "U3") (pin "8") (pinfunction "VIN_8") (pintype "unspecified"))
      (node (ref "U5") (pin "8") (pinfunction "VIN_8") (pintype "unspecified"))
    )
    (net (code "80") (name "VREF") (class "Default")
      (node (ref "C2") (pin "1") (pinfunction "1_1") (pintype "unspecified"))
      (node (ref "C50") (pin "1") (pinfunction "1_1") (pintype "unspecified"))
      (node (ref "C51") (pin "2") (pinfunction "2_2") (pintype "unspecified"))
      (node (ref "U12") (pin "3") (pinfunction "2_3") (pintype "unspecified"))
    )
    (net (code "81") (name "unconnected-(P1-8-Pad4)") (class "Default")
      (node (ref "P1") (pin "4") (pinfunction "8_4") (pintype "unspecified"))
    )
    (net (code "82") (name "unconnected-(P1-Pad6)") (class "Default")
      (node (ref "P1") (pin "6") (pinfunction "6_6") (pintype "unspecified"))
    )
    (net (code "83") (name "unconnected-(U1-FAULTZ-Pad3)") (class "Default")
      (node (ref "U1") (pin "3") (pinfunction "FAULTZ_3") (pintype "unspecified"))
    )
    (net (code "84") (name "unconnected-(U1-OUTNR-Pad27)") (class "Default")
      (node (ref "U1") (pin "27") (pinfunction "OUTNR_27") (pintype "unspecified"))
    )
    (net (code "85") (name "unconnected-(U2-DIAGNOSTICS-Pad10)") (class "Default")
      (node (ref "U2") (pin "10") (pinfunction "DIAGNOSTICS_10") (pintype "unspecified"))
    )
    (net (code "86") (name "unconnected-(U3-NC-Pad4)") (class "Default")
      (node (ref "U3") (pin "4") (pinfunction "NC_4") (pintype "unspecified"))
    )
    (net (code "87") (name "unconnected-(U3-NC-Pad5)") (class "Default")
      (node (ref "U3") (pin "5") (pinfunction "NC_5") (pintype "unspecified"))
    )
    (net (code "88") (name "unconnected-(U4-PadRING2)") (class "Default")
      (node (ref "U4") (pin "RING2") (pinfunction "RING2_RING2") (pintype "unspecified"))
    )
    (net (code "89") (name "unconnected-(U5-NC-Pad4)") (class "Default")
      (node (ref "U5") (pin "4") (pinfunction "NC_4") (pintype "unspecified"))
    )
    (net (code "90") (name "unconnected-(U5-NC-Pad5)") (class "Default")
      (node (ref "U5") (pin "5") (pinfunction "NC_5") (pintype "unspecified"))
    )
    (net (code "91") (name "unconnected-(U12-4-Pad7)") (class "Default")
      (node (ref "U12") (pin "7") (pinfunction "4_7") (pintype "unspecified"))
    )
    (net (code "92") (name "unconnected-(U12-5-Pad9)") (class "Default")
      (node (ref "U12") (pin "9") (pinfunction "5_9") (pintype "unspecified"))
    )
    (net (code "93") (name "unconnected-(U12-15-Pad8)") (class "Default")
      (node (ref "U12") (pin "8") (pinfunction "15_8") (pintype "unspecified"))
    )
    (net (code "94") (name "unconnected-(U12-16-Pad6)") (class "Default")
      (node (ref "U12") (pin "6") (pinfunction "16_6") (pintype "unspecified"))
    )
    (net (code "95") (name "unconnected-(U12-18-Pad2)") (class "Default")
      (node (ref "U12") (pin "2") (pinfunction "18_2") (pintype "unspecified"))
    )
  )
)
